# leanerModule.net
KiCad netlist of a schematic drawn in EAGLE
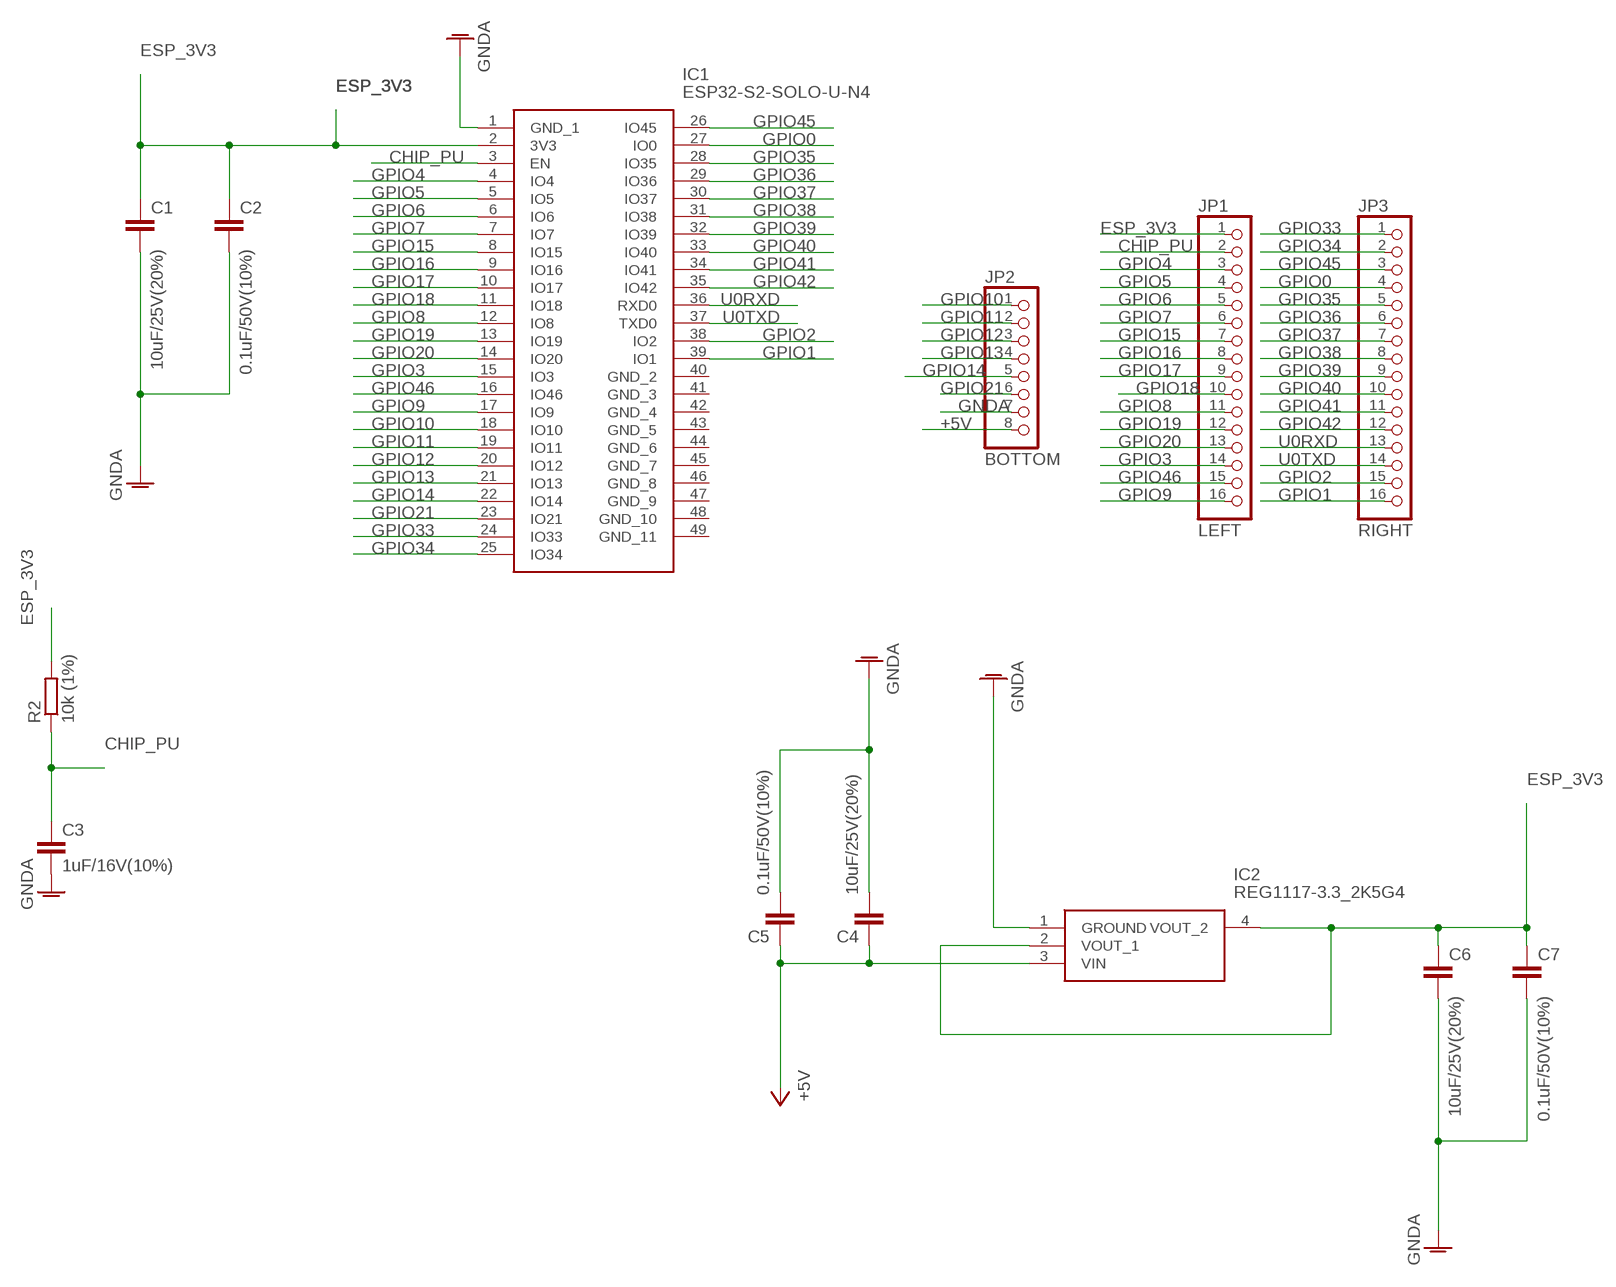
[diagram p0: schematic, sheet 1]

(export (version "E")
  (design (tool "Eeschema 10.0.6"))
  (components
    (comp (ref "C1")
      (value "10uF/25V(20%)")
      (footprint "eagle-import:C0805")
      (libsource (lib "eagle-import") (part "C-EUC0805"))
    )
    (comp (ref "C2")
      (value "0.1uF/50V(10%)")
      (footprint "eagle-import:C0805")
      (libsource (lib "eagle-import") (part "C-EUC0805"))
    )
    (comp (ref "C3")
      (value "1uF/16V(10%)")
      (footprint "eagle-import:C0805")
      (libsource (lib "eagle-import") (part "C-EUC0805"))
    )
    (comp (ref "C4")
      (value "10uF/25V(20%)")
      (footprint "eagle-import:C0805")
      (libsource (lib "eagle-import") (part "C-EUC0805"))
    )
    (comp (ref "C5")
      (value "0.1uF/50V(10%)")
      (footprint "eagle-import:C0805")
      (libsource (lib "eagle-import") (part "C-EUC0805"))
    )
    (comp (ref "C6")
      (value "10uF/25V(20%)")
      (footprint "eagle-import:C0805")
      (libsource (lib "eagle-import") (part "C-EUC0805"))
    )
    (comp (ref "C7")
      (value "0.1uF/50V(10%)")
      (footprint "eagle-import:C0805")
      (libsource (lib "eagle-import") (part "C-EUC0805"))
    )
    (comp (ref "IC1")
      (value "ESP32-S2-SOLO-U-N4")
      (footprint "eagle-import:ESP32S2SOLOUN4")
      (fields (field (name "MOUSER_PART_NUMBER") "356-ESP32-S2-SOLOUN4"))
      (libsource (lib "eagle-import") (part "ESP32-S2-SOLO-U-N4"))
    )
    (comp (ref "IC2")
      (value "REG1117-3.3_2K5G4")
      (footprint "eagle-import:SOT230P700X180-4N")
      (fields
        (field (name "MANUFACTURER_PART_NUMBER") "REG1117-3.3/2K5G4")
        (field (name "MOUSER_PART_NUMBER") "595-REG1117332K5G4")
      )
      (libsource (lib "eagle-import") (part "REG1117-3.3_2K5G4"))
    )
    (comp (ref "JP1")
      (value "LEFT")
      (footprint "eagle-import:1X16")
      (libsource (lib "eagle-import") (part "PINHD-1X16"))
    )
    (comp (ref "JP2")
      (value "BOTTOM")
      (footprint "eagle-import:1X08")
      (libsource (lib "eagle-import") (part "PINHD-1X8"))
    )
    (comp (ref "JP3")
      (value "RIGHT")
      (footprint "eagle-import:1X16")
      (libsource (lib "eagle-import") (part "PINHD-1X16"))
    )
    (comp (ref "R2")
      (value "10k (1%)")
      (footprint "eagle-import:R0603")
      (libsource (lib "eagle-import") (part "R-EU_R0603"))
    )
  )
  (nets
    (net (code "1") (name "+5V") (class "Default")
      (node (ref "C4") (pin "1") (pinfunction "1_1") (pintype "passive"))
      (node (ref "C5") (pin "1") (pinfunction "1_1") (pintype "passive"))
      (node (ref "IC2") (pin "3") (pinfunction "VIN_3") (pintype "bidirectional"))
      (node (ref "JP2") (pin "8") (pinfunction "8_8") (pintype "passive"))
    )
    (net (code "2") (name "/CHIP_PU") (class "Default")
      (node (ref "C3") (pin "1") (pinfunction "1_1") (pintype "passive"))
      (node (ref "IC1") (pin "3") (pinfunction "EN_3") (pintype "bidirectional"))
      (node (ref "JP1") (pin "2") (pinfunction "2_2") (pintype "passive"))
      (node (ref "R2") (pin "1") (pinfunction "1_1") (pintype "passive"))
    )
    (net (code "3") (name "/ESP_3V3") (class "Default")
      (node (ref "C1") (pin "1") (pinfunction "1_1") (pintype "passive"))
      (node (ref "C2") (pin "1") (pinfunction "1_1") (pintype "passive"))
      (node (ref "C6") (pin "1") (pinfunction "1_1") (pintype "passive"))
      (node (ref "C7") (pin "1") (pinfunction "1_1") (pintype "passive"))
      (node (ref "IC1") (pin "2") (pinfunction "3V3_2") (pintype "bidirectional"))
      (node (ref "IC2") (pin "2") (pinfunction "VOUT_1_2") (pintype "bidirectional"))
      (node (ref "IC2") (pin "4") (pinfunction "VOUT_2_4") (pintype "bidirectional"))
      (node (ref "JP1") (pin "1") (pinfunction "1_1") (pintype "passive"))
      (node (ref "R2") (pin "2") (pinfunction "2_2") (pintype "passive"))
    )
    (net (code "4") (name "/GPIO0") (class "Default")
      (node (ref "IC1") (pin "27") (pinfunction "IO0_27") (pintype "bidirectional"))
      (node (ref "JP3") (pin "4") (pinfunction "4_4") (pintype "passive"))
    )
    (net (code "5") (name "/GPIO1") (class "Default")
      (node (ref "IC1") (pin "39") (pinfunction "IO1_39") (pintype "bidirectional"))
      (node (ref "JP3") (pin "16") (pinfunction "16_16") (pintype "passive"))
    )
    (net (code "6") (name "/GPIO2") (class "Default")
      (node (ref "IC1") (pin "38") (pinfunction "IO2_38") (pintype "bidirectional"))
      (node (ref "JP3") (pin "15") (pinfunction "15_15") (pintype "passive"))
    )
    (net (code "7") (name "/GPIO3") (class "Default")
      (node (ref "IC1") (pin "15") (pinfunction "IO3_15") (pintype "bidirectional"))
      (node (ref "JP1") (pin "14") (pinfunction "14_14") (pintype "passive"))
    )
    (net (code "8") (name "/GPIO4") (class "Default")
      (node (ref "IC1") (pin "4") (pinfunction "IO4_4") (pintype "bidirectional"))
      (node (ref "JP1") (pin "3") (pinfunction "3_3") (pintype "passive"))
    )
    (net (code "9") (name "/GPIO5") (class "Default")
      (node (ref "IC1") (pin "5") (pinfunction "IO5_5") (pintype "bidirectional"))
      (node (ref "JP1") (pin "4") (pinfunction "4_4") (pintype "passive"))
    )
    (net (code "10") (name "/GPIO6") (class "Default")
      (node (ref "IC1") (pin "6") (pinfunction "IO6_6") (pintype "bidirectional"))
      (node (ref "JP1") (pin "5") (pinfunction "5_5") (pintype "passive"))
    )
    (net (code "11") (name "/GPIO7") (class "Default")
      (node (ref "IC1") (pin "7") (pinfunction "IO7_7") (pintype "bidirectional"))
      (node (ref "JP1") (pin "6") (pinfunction "6_6") (pintype "passive"))
    )
    (net (code "12") (name "/GPIO8") (class "Default")
      (node (ref "IC1") (pin "12") (pinfunction "IO8_12") (pintype "bidirectional"))
      (node (ref "JP1") (pin "11") (pinfunction "11_11") (pintype "passive"))
    )
    (net (code "13") (name "/GPIO9") (class "Default")
      (node (ref "IC1") (pin "17") (pinfunction "IO9_17") (pintype "bidirectional"))
      (node (ref "JP1") (pin "16") (pinfunction "16_16") (pintype "passive"))
    )
    (net (code "14") (name "/GPIO10") (class "Default")
      (node (ref "IC1") (pin "18") (pinfunction "IO10_18") (pintype "bidirectional"))
      (node (ref "JP2") (pin "1") (pinfunction "1_1") (pintype "passive"))
    )
    (net (code "15") (name "/GPIO11") (class "Default")
      (node (ref "IC1") (pin "19") (pinfunction "IO11_19") (pintype "bidirectional"))
      (node (ref "JP2") (pin "2") (pinfunction "2_2") (pintype "passive"))
    )
    (net (code "16") (name "/GPIO12") (class "Default")
      (node (ref "IC1") (pin "20") (pinfunction "IO12_20") (pintype "bidirectional"))
      (node (ref "JP2") (pin "3") (pinfunction "3_3") (pintype "passive"))
    )
    (net (code "17") (name "/GPIO13") (class "Default")
      (node (ref "IC1") (pin "21") (pinfunction "IO13_21") (pintype "bidirectional"))
      (node (ref "JP2") (pin "4") (pinfunction "4_4") (pintype "passive"))
    )
    (net (code "18") (name "/GPIO14") (class "Default")
      (node (ref "IC1") (pin "22") (pinfunction "IO14_22") (pintype "bidirectional"))
      (node (ref "JP2") (pin "5") (pinfunction "5_5") (pintype "passive"))
    )
    (net (code "19") (name "/GPIO15") (class "Default")
      (node (ref "IC1") (pin "8") (pinfunction "IO15_8") (pintype "bidirectional"))
      (node (ref "JP1") (pin "7") (pinfunction "7_7") (pintype "passive"))
    )
    (net (code "20") (name "/GPIO16") (class "Default")
      (node (ref "IC1") (pin "9") (pinfunction "IO16_9") (pintype "bidirectional"))
      (node (ref "JP1") (pin "8") (pinfunction "8_8") (pintype "passive"))
    )
    (net (code "21") (name "/GPIO17") (class "Default")
      (node (ref "IC1") (pin "10") (pinfunction "IO17_10") (pintype "bidirectional"))
      (node (ref "JP1") (pin "9") (pinfunction "9_9") (pintype "passive"))
    )
    (net (code "22") (name "/GPIO18") (class "Default")
      (node (ref "IC1") (pin "11") (pinfunction "IO18_11") (pintype "bidirectional"))
      (node (ref "JP1") (pin "10") (pinfunction "10_10") (pintype "passive"))
    )
    (net (code "23") (name "/GPIO19") (class "Default")
      (node (ref "IC1") (pin "13") (pinfunction "IO19_13") (pintype "bidirectional"))
      (node (ref "JP1") (pin "12") (pinfunction "12_12") (pintype "passive"))
    )
    (net (code "24") (name "/GPIO20") (class "Default")
      (node (ref "IC1") (pin "14") (pinfunction "IO20_14") (pintype "bidirectional"))
      (node (ref "JP1") (pin "13") (pinfunction "13_13") (pintype "passive"))
    )
    (net (code "25") (name "/GPIO21") (class "Default")
      (node (ref "IC1") (pin "23") (pinfunction "IO21_23") (pintype "bidirectional"))
      (node (ref "JP2") (pin "6") (pinfunction "6_6") (pintype "passive"))
    )
    (net (code "26") (name "/GPIO33") (class "Default")
      (node (ref "IC1") (pin "24") (pinfunction "IO33_24") (pintype "bidirectional"))
      (node (ref "JP3") (pin "1") (pinfunction "1_1") (pintype "passive"))
    )
    (net (code "27") (name "/GPIO34") (class "Default")
      (node (ref "IC1") (pin "25") (pinfunction "IO34_25") (pintype "bidirectional"))
      (node (ref "JP3") (pin "2") (pinfunction "2_2") (pintype "passive"))
    )
    (net (code "28") (name "/GPIO35") (class "Default")
      (node (ref "IC1") (pin "28") (pinfunction "IO35_28") (pintype "bidirectional"))
      (node (ref "JP3") (pin "5") (pinfunction "5_5") (pintype "passive"))
    )
    (net (code "29") (name "/GPIO36") (class "Default")
      (node (ref "IC1") (pin "29") (pinfunction "IO36_29") (pintype "bidirectional"))
      (node (ref "JP3") (pin "6") (pinfunction "6_6") (pintype "passive"))
    )
    (net (code "30") (name "/GPIO37") (class "Default")
      (node (ref "IC1") (pin "30") (pinfunction "IO37_30") (pintype "bidirectional"))
      (node (ref "JP3") (pin "7") (pinfunction "7_7") (pintype "passive"))
    )
    (net (code "31") (name "/GPIO38") (class "Default")
      (node (ref "IC1") (pin "31") (pinfunction "IO38_31") (pintype "bidirectional"))
      (node (ref "JP3") (pin "8") (pinfunction "8_8") (pintype "passive"))
    )
    (net (code "32") (name "/GPIO39") (class "Default")
      (node (ref "IC1") (pin "32") (pinfunction "IO39_32") (pintype "bidirectional"))
      (node (ref "JP3") (pin "9") (pinfunction "9_9") (pintype "passive"))
    )
    (net (code "33") (name "/GPIO40") (class "Default")
      (node (ref "IC1") (pin "33") (pinfunction "IO40_33") (pintype "bidirectional"))
      (node (ref "JP3") (pin "10") (pinfunction "10_10") (pintype "passive"))
    )
    (net (code "34") (name "/GPIO41") (class "Default")
      (node (ref "IC1") (pin "34") (pinfunction "IO41_34") (pintype "bidirectional"))
      (node (ref "JP3") (pin "11") (pinfunction "11_11") (pintype "passive"))
    )
    (net (code "35") (name "/GPIO42") (class "Default")
      (node (ref "IC1") (pin "35") (pinfunction "IO42_35") (pintype "bidirectional"))
      (node (ref "JP3") (pin "12") (pinfunction "12_12") (pintype "passive"))
    )
    (net (code "36") (name "/GPIO45") (class "Default")
      (node (ref "IC1") (pin "26") (pinfunction "IO45_26") (pintype "bidirectional"))
      (node (ref "JP3") (pin "3") (pinfunction "3_3") (pintype "passive"))
    )
    (net (code "37") (name "/GPIO46") (class "Default")
      (node (ref "IC1") (pin "16") (pinfunction "IO46_16") (pintype "bidirectional"))
      (node (ref "JP1") (pin "15") (pinfunction "15_15") (pintype "passive"))
    )
    (net (code "38") (name "/U0RXD") (class "Default")
      (node (ref "IC1") (pin "36") (pinfunction "RXD0_36") (pintype "bidirectional"))
      (node (ref "JP3") (pin "13") (pinfunction "13_13") (pintype "passive"))
    )
    (net (code "39") (name "/U0TXD") (class "Default")
      (node (ref "IC1") (pin "37") (pinfunction "TXD0_37") (pintype "bidirectional"))
      (node (ref "JP3") (pin "14") (pinfunction "14_14") (pintype "passive"))
    )
    (net (code "40") (name "GNDA") (class "Default")
      (node (ref "C1") (pin "2") (pinfunction "2_2") (pintype "passive"))
      (node (ref "C2") (pin "2") (pinfunction "2_2") (pintype "passive"))
      (node (ref "C3") (pin "2") (pinfunction "2_2") (pintype "passive"))
      (node (ref "C4") (pin "2") (pinfunction "2_2") (pintype "passive"))
      (node (ref "C5") (pin "2") (pinfunction "2_2") (pintype "passive"))
      (node (ref "C6") (pin "2") (pinfunction "2_2") (pintype "passive"))
      (node (ref "C7") (pin "2") (pinfunction "2_2") (pintype "passive"))
      (node (ref "IC1") (pin "1") (pinfunction "GND_1_1") (pintype "bidirectional"))
      (node (ref "IC2") (pin "1") (pinfunction "GROUND_1") (pintype "bidirectional"))
      (node (ref "JP2") (pin "7") (pinfunction "7_7") (pintype "passive"))
    )
    (net (code "41") (name "unconnected-(IC1-GND_2-Pad40)") (class "Default")
      (node (ref "IC1") (pin "40") (pinfunction "GND_2_40") (pintype "bidirectional"))
    )
    (net (code "42") (name "unconnected-(IC1-GND_3-Pad41)") (class "Default")
      (node (ref "IC1") (pin "41") (pinfunction "GND_3_41") (pintype "bidirectional"))
    )
    (net (code "43") (name "unconnected-(IC1-GND_4-Pad42)") (class "Default")
      (node (ref "IC1") (pin "42") (pinfunction "GND_4_42") (pintype "bidirectional"))
    )
    (net (code "44") (name "unconnected-(IC1-GND_5-Pad43)") (class "Default")
      (node (ref "IC1") (pin "43") (pinfunction "GND_5_43") (pintype "bidirectional"))
    )
    (net (code "45") (name "unconnected-(IC1-GND_6-Pad44)") (class "Default")
      (node (ref "IC1") (pin "44") (pinfunction "GND_6_44") (pintype "bidirectional"))
    )
    (net (code "46") (name "unconnected-(IC1-GND_7-Pad45)") (class "Default")
      (node (ref "IC1") (pin "45") (pinfunction "GND_7_45") (pintype "bidirectional"))
    )
    (net (code "47") (name "unconnected-(IC1-GND_8-Pad46)") (class "Default")
      (node (ref "IC1") (pin "46") (pinfunction "GND_8_46") (pintype "bidirectional"))
    )
    (net (code "48") (name "unconnected-(IC1-GND_9-Pad47)") (class "Default")
      (node (ref "IC1") (pin "47") (pinfunction "GND_9_47") (pintype "bidirectional"))
    )
    (net (code "49") (name "unconnected-(IC1-GND_10-Pad48)") (class "Default")
      (node (ref "IC1") (pin "48") (pinfunction "GND_10_48") (pintype "bidirectional"))
    )
    (net (code "50") (name "unconnected-(IC1-GND_11-Pad49)") (class "Default")
      (node (ref "IC1") (pin "49") (pinfunction "GND_11_49") (pintype "bidirectional"))
    )
  )
)
